# 19_-CAMERA_PWR_CONNECTORS.net
KiCad netlist of a schematic drawn in Altium Designer
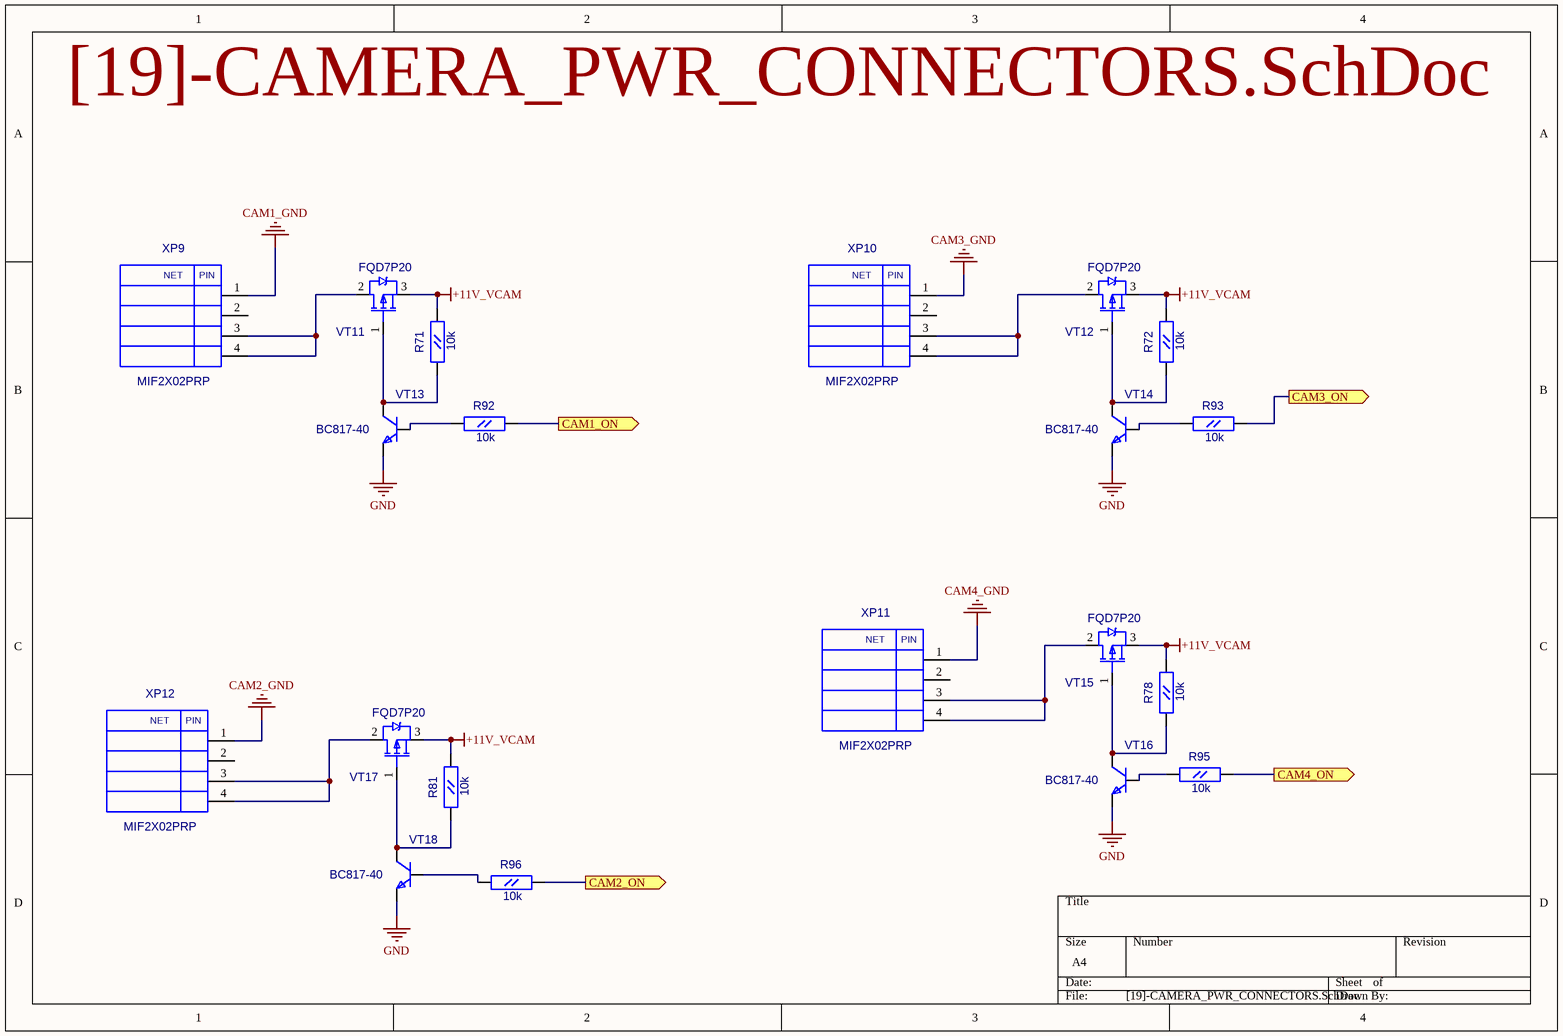
[diagram p0: [19]-CAMERA_PWR_CONNECTORS.SchDoc]

(export (version "E")
  (design (tool "Eeschema 10.0.6"))
  (components
    (comp (ref "R71")
      (value "10k")
      (footprint "RC0603")
      (description "RC0603")
      (libsource (lib "fizik_lib") (part "RC0603"))
    )
    (comp (ref "R72")
      (value "10k")
      (footprint "RC0603")
      (description "RC0603")
      (libsource (lib "fizik_lib") (part "RC0603"))
    )
    (comp (ref "R78")
      (value "10k")
      (footprint "RC0603")
      (description "RC0603")
      (libsource (lib "fizik_lib") (part "RC0603"))
    )
    (comp (ref "R81")
      (value "10k")
      (footprint "RC0603")
      (description "RC0603")
      (libsource (lib "fizik_lib") (part "RC0603"))
    )
    (comp (ref "R92")
      (value "10k")
      (footprint "RC0603")
      (description "RC0603")
      (libsource (lib "fizik_lib") (part "RC0603"))
    )
    (comp (ref "R93")
      (value "10k")
      (footprint "RC0603")
      (description "RC0603")
      (libsource (lib "fizik_lib") (part "RC0603"))
    )
    (comp (ref "R95")
      (value "10k")
      (footprint "RC0603")
      (description "RC0603")
      (libsource (lib "fizik_lib") (part "RC0603"))
    )
    (comp (ref "R96")
      (value "10k")
      (footprint "RC0603")
      (description "RC0603")
      (libsource (lib "fizik_lib") (part "RC0603"))
    )
    (comp (ref "VT11")
      (value "FQD7P20")
      (footprint "D-PAK(TO-252AA)")
      (description "HEXFET Power MOSFET")
      (libsource (lib "gprs_modem_2") (part "IRFR9220"))
    )
    (comp (ref "VT12")
      (value "FQD7P20")
      (footprint "D-PAK(TO-252AA)")
      (description "HEXFET Power MOSFET")
      (libsource (lib "gprs_modem_2") (part "IRFR9220"))
    )
    (comp (ref "VT13")
      (value "BC817-40")
      (footprint "SOT-23(123)")
      (description "NPN 500ma transistor")
      (libsource (lib "fizik_lib") (part "BC846BLT1"))
    )
    (comp (ref "VT14")
      (value "BC817-40")
      (footprint "SOT-23(123)")
      (description "NPN 500ma transistor")
      (libsource (lib "fizik_lib") (part "BC846BLT1"))
    )
    (comp (ref "VT15")
      (value "FQD7P20")
      (footprint "D-PAK(TO-252AA)")
      (description "HEXFET Power MOSFET")
      (libsource (lib "gprs_modem_2") (part "IRFR9220"))
    )
    (comp (ref "VT16")
      (value "BC817-40")
      (footprint "SOT-23(123)")
      (description "NPN 500ma transistor")
      (libsource (lib "fizik_lib") (part "BC846BLT1"))
    )
    (comp (ref "VT17")
      (value "FQD7P20")
      (footprint "D-PAK(TO-252AA)")
      (description "HEXFET Power MOSFET")
      (libsource (lib "gprs_modem_2") (part "IRFR9220"))
    )
    (comp (ref "VT18")
      (value "BC817-40")
      (footprint "SOT-23(123)")
      (description "NPN 500ma transistor")
      (libsource (lib "fizik_lib") (part "BC846BLT1"))
    )
    (comp (ref "XP9")
      (value "MIF2X02PRP")
      (footprint "MIF2X02PRP")
      (libsource (lib "fizik_lib") (part "MIF2X02PRP"))
    )
    (comp (ref "XP10")
      (value "MIF2X02PRP")
      (footprint "MIF2X02PRP")
      (libsource (lib "fizik_lib") (part "MIF2X02PRP"))
    )
    (comp (ref "XP11")
      (value "MIF2X02PRP")
      (footprint "MIF2X02PRP")
      (libsource (lib "fizik_lib") (part "MIF2X02PRP"))
    )
    (comp (ref "XP12")
      (value "MIF2X02PRP")
      (footprint "MIF2X02PRP")
      (libsource (lib "fizik_lib") (part "MIF2X02PRP"))
    )
  )
  (nets
    (net (code "1") (name "+11V_VCAM") (class "Default")
      (node (ref "R71") (pin "2") (pinfunction "B_2") (pintype "passive"))
      (node (ref "R72") (pin "2") (pinfunction "B_2") (pintype "passive"))
      (node (ref "R78") (pin "2") (pinfunction "B_2") (pintype "passive"))
      (node (ref "R81") (pin "2") (pinfunction "B_2") (pintype "passive"))
      (node (ref "VT11") (pin "3") (pinfunction "S_3") (pintype "passive"))
      (node (ref "VT12") (pin "3") (pinfunction "S_3") (pintype "passive"))
      (node (ref "VT15") (pin "3") (pinfunction "S_3") (pintype "passive"))
      (node (ref "VT17") (pin "3") (pinfunction "S_3") (pintype "passive"))
    )
    (net (code "2") (name "/CAM1_ON") (class "Default")
      (node (ref "R92") (pin "2") (pinfunction "B_2") (pintype "passive"))
    )
    (net (code "3") (name "/CAM2_ON") (class "Default")
      (node (ref "R96") (pin "2") (pinfunction "B_2") (pintype "passive"))
    )
    (net (code "4") (name "/CAM3_ON") (class "Default")
      (node (ref "R93") (pin "2") (pinfunction "B_2") (pintype "passive"))
    )
    (net (code "5") (name "/CAM4_ON") (class "Default")
      (node (ref "R95") (pin "2") (pinfunction "B_2") (pintype "passive"))
    )
    (net (code "6") (name "CAM1_GND") (class "Default")
      (node (ref "XP9") (pin "1") (pinfunction "1_1") (pintype "passive"))
    )
    (net (code "7") (name "CAM2_GND") (class "Default")
      (node (ref "XP12") (pin "1") (pinfunction "1_1") (pintype "passive"))
    )
    (net (code "8") (name "CAM3_GND") (class "Default")
      (node (ref "XP10") (pin "1") (pinfunction "1_1") (pintype "passive"))
    )
    (net (code "9") (name "CAM4_GND") (class "Default")
      (node (ref "XP11") (pin "1") (pinfunction "1_1") (pintype "passive"))
    )
    (net (code "10") (name "GND") (class "Default")
      (node (ref "VT13") (pin "2") (pinfunction "E_2") (pintype "passive"))
      (node (ref "VT14") (pin "2") (pinfunction "E_2") (pintype "passive"))
      (node (ref "VT16") (pin "2") (pinfunction "E_2") (pintype "passive"))
      (node (ref "VT18") (pin "2") (pinfunction "E_2") (pintype "passive"))
    )
    (net (code "11") (name "Net-(R71-A)") (class "Default")
      (node (ref "R71") (pin "1") (pinfunction "A_1") (pintype "passive"))
      (node (ref "VT11") (pin "1") (pinfunction "G_1") (pintype "passive"))
      (node (ref "VT13") (pin "3") (pinfunction "C_3") (pintype "passive"))
    )
    (net (code "12") (name "Net-(R72-A)") (class "Default")
      (node (ref "R72") (pin "1") (pinfunction "A_1") (pintype "passive"))
      (node (ref "VT12") (pin "1") (pinfunction "G_1") (pintype "passive"))
      (node (ref "VT14") (pin "3") (pinfunction "C_3") (pintype "passive"))
    )
    (net (code "13") (name "Net-(R78-A)") (class "Default")
      (node (ref "R78") (pin "1") (pinfunction "A_1") (pintype "passive"))
      (node (ref "VT15") (pin "1") (pinfunction "G_1") (pintype "passive"))
      (node (ref "VT16") (pin "3") (pinfunction "C_3") (pintype "passive"))
    )
    (net (code "14") (name "Net-(R81-A)") (class "Default")
      (node (ref "R81") (pin "1") (pinfunction "A_1") (pintype "passive"))
      (node (ref "VT17") (pin "1") (pinfunction "G_1") (pintype "passive"))
      (node (ref "VT18") (pin "3") (pinfunction "C_3") (pintype "passive"))
    )
    (net (code "15") (name "Net-(R92-A)") (class "Default")
      (node (ref "R92") (pin "1") (pinfunction "A_1") (pintype "passive"))
      (node (ref "VT13") (pin "1") (pinfunction "B_1") (pintype "passive"))
    )
    (net (code "16") (name "Net-(R93-A)") (class "Default")
      (node (ref "R93") (pin "1") (pinfunction "A_1") (pintype "passive"))
      (node (ref "VT14") (pin "1") (pinfunction "B_1") (pintype "passive"))
    )
    (net (code "17") (name "Net-(R95-A)") (class "Default")
      (node (ref "R95") (pin "1") (pinfunction "A_1") (pintype "passive"))
      (node (ref "VT16") (pin "1") (pinfunction "B_1") (pintype "passive"))
    )
    (net (code "18") (name "Net-(R96-A)") (class "Default")
      (node (ref "R96") (pin "1") (pinfunction "A_1") (pintype "passive"))
      (node (ref "VT18") (pin "1") (pinfunction "B_1") (pintype "passive"))
    )
    (net (code "19") (name "Net-(VT11-D)") (class "Default")
      (node (ref "VT11") (pin "2") (pinfunction "D_2") (pintype "passive"))
      (node (ref "XP9") (pin "3") (pinfunction "3_3") (pintype "passive"))
      (node (ref "XP9") (pin "4") (pinfunction "4_4") (pintype "passive"))
    )
    (net (code "20") (name "Net-(VT12-D)") (class "Default")
      (node (ref "VT12") (pin "2") (pinfunction "D_2") (pintype "passive"))
      (node (ref "XP10") (pin "3") (pinfunction "3_3") (pintype "passive"))
      (node (ref "XP10") (pin "4") (pinfunction "4_4") (pintype "passive"))
    )
    (net (code "21") (name "Net-(VT15-D)") (class "Default")
      (node (ref "VT15") (pin "2") (pinfunction "D_2") (pintype "passive"))
      (node (ref "XP11") (pin "3") (pinfunction "3_3") (pintype "passive"))
      (node (ref "XP11") (pin "4") (pinfunction "4_4") (pintype "passive"))
    )
    (net (code "22") (name "Net-(VT17-D)") (class "Default")
      (node (ref "VT17") (pin "2") (pinfunction "D_2") (pintype "passive"))
      (node (ref "XP12") (pin "3") (pinfunction "3_3") (pintype "passive"))
      (node (ref "XP12") (pin "4") (pinfunction "4_4") (pintype "passive"))
    )
    (net (code "23") (name "unconnected-(XP9-Pad2)") (class "Default")
      (node (ref "XP9") (pin "2") (pinfunction "2_2") (pintype "passive"))
    )
    (net (code "24") (name "unconnected-(XP10-Pad2)") (class "Default")
      (node (ref "XP10") (pin "2") (pinfunction "2_2") (pintype "passive"))
    )
    (net (code "25") (name "unconnected-(XP11-Pad2)") (class "Default")
      (node (ref "XP11") (pin "2") (pinfunction "2_2") (pintype "passive"))
    )
    (net (code "26") (name "unconnected-(XP12-Pad2)") (class "Default")
      (node (ref "XP12") (pin "2") (pinfunction "2_2") (pintype "passive"))
    )
  )
)
